# Antenna_Supervisory_Circuit.net
KiCad netlist of a schematic drawn in Altium Designer
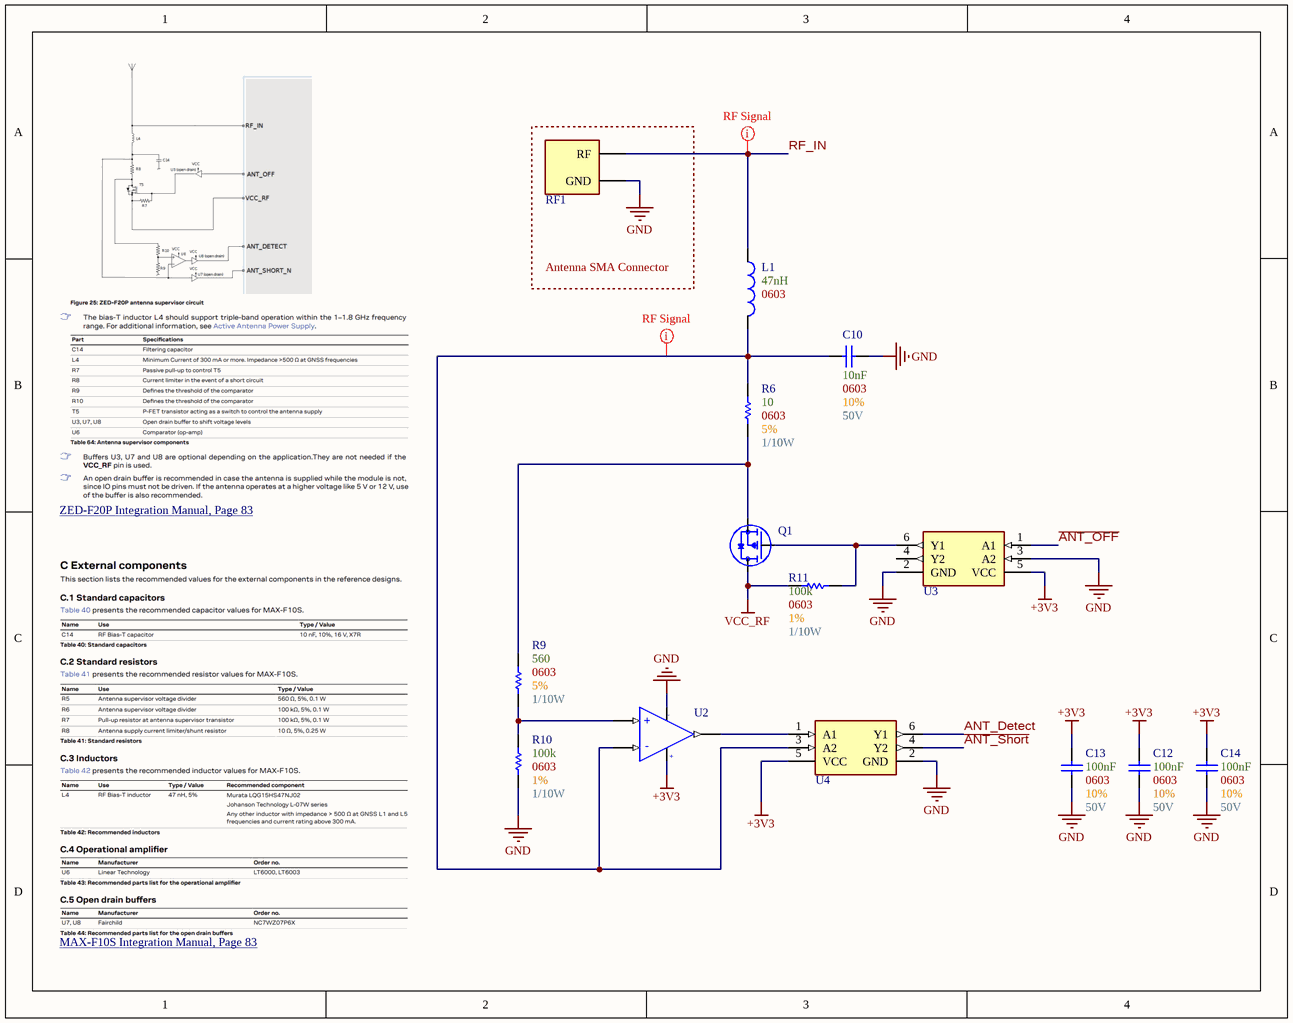
[diagram p0: Antenna Supervisory Circuit.SchDoc]

(export (version "E")
  (design (tool "Eeschema 10.0.6"))
  (components
    (comp (ref "C10")
      (value "[Cap] 0603 0.01uF 10% 50V")
      (footprint "[Cap] SMD 0603")
      (description "C0603C103K5RACTU")
      (fields
        (field (name "MAX VOLTAGE") "50V")
        (field (name "SIZE PACKAGE") "0603")
        (field (name "TOLERANCE") "10%")
        (field (name "CAPACITANCE") "10nF")
      )
      (libsource (lib "Capacitors") (part "[Cap] 0603 0.01uF 10% 50V"))
    )
    (comp (ref "C12")
      (value "[Cap] 0603 0.1uF 10% 50V")
      (footprint "[Cap] SMD 0603")
      (description "CL10B104KB8NNNC")
      (fields
        (field (name "MAX VOLTAGE") "50V")
        (field (name "SIZE PACKAGE") "0603")
        (field (name "TOLERANCE") "10%")
        (field (name "CAPACITANCE") "100nF")
      )
      (libsource (lib "Capacitors") (part "[Cap] 0603 0.1uF 10% 50V"))
    )
    (comp (ref "C13")
      (value "[Cap] 0603 0.1uF 10% 50V")
      (footprint "[Cap] SMD 0603")
      (description "CL10B104KB8NNNC")
      (fields
        (field (name "MAX VOLTAGE") "50V")
        (field (name "SIZE PACKAGE") "0603")
        (field (name "TOLERANCE") "10%")
        (field (name "CAPACITANCE") "100nF")
      )
      (libsource (lib "Capacitors") (part "[Cap] 0603 0.1uF 10% 50V"))
    )
    (comp (ref "C14")
      (value "[Cap] 0603 0.1uF 10% 50V")
      (footprint "[Cap] SMD 0603")
      (description "CL10B104KB8NNNC")
      (fields
        (field (name "MAX VOLTAGE") "50V")
        (field (name "SIZE PACKAGE") "0603")
        (field (name "TOLERANCE") "10%")
        (field (name "CAPACITANCE") "100nF")
      )
      (libsource (lib "Capacitors") (part "[Cap] 0603 0.1uF 10% 50V"))
    )
    (comp (ref "L1")
      (value "[47nH] SMD 0603 90mA")
      (footprint "[Inductor] SMD 0603")
      (description "AIMC-0603-47NJ-T")
      (fields (field (name "PACKAGE") "0603") (field (name "INDUCTANCE") "47nH"))
      (libsource (lib "Inductors") (part "[47nH] SMD 0603 90mA"))
    )
    (comp (ref "Q1")
      (value "[PMOS] SMD 20V 1A 200mOhm")
      (footprint "SOT323")
      (description "PMF170XP,115")
      (libsource (lib "Transistors") (part "[PMOS] SMD 20V 1A 200mOhm"))
    )
    (comp (ref "R6")
      (value "[10] SMD 0603 5% 1/10W")
      (footprint "[Res] SMD 0603")
      (description "RC0603JR-1310RL")
      (fields
        (field (name "WATTAGE") "1/10W")
        (field (name "TOLERANCE") "5%")
        (field (name "RESISTANCE") "10")
        (field (name "SIZE PACKAGE") "0603")
      )
      (libsource (lib "Resistors") (part "[10] SMD 0603 5% 1/10W"))
    )
    (comp (ref "R9")
      (value "[560] SMD 0603 5% 1/10W")
      (footprint "[Res] SMD 0603")
      (description "RC0603JR-07560RL")
      (fields
        (field (name "WATTAGE") "1/10W")
        (field (name "TOLERANCE") "5%")
        (field (name "RESISTANCE") "560")
        (field (name "SIZE PACKAGE") "0603")
      )
      (libsource (lib "Resistors") (part "[560] SMD 0603 5% 1/10W"))
    )
    (comp (ref "R10")
      (value "[100k] SMD 0603 1% 1/10W")
      (footprint "[Res] SMD 0603")
      (description "RC0603FR-07100KL")
      (fields
        (field (name "WATTAGE") "1/10W")
        (field (name "TOLERANCE") "1%")
        (field (name "RESISTANCE") "100k")
        (field (name "SIZE PACKAGE") "0603")
      )
      (libsource (lib "Resistors") (part "[100k] SMD 0603 1% 1/10W"))
    )
    (comp (ref "R11")
      (value "[100k] SMD 0603 1% 1/10W")
      (footprint "[Res] SMD 0603")
      (description "RC0603FR-07100KL")
      (fields
        (field (name "WATTAGE") "1/10W")
        (field (name "TOLERANCE") "1%")
        (field (name "RESISTANCE") "100k")
        (field (name "SIZE PACKAGE") "0603")
      )
      (libsource (lib "Resistors") (part "[100k] SMD 0603 1% 1/10W"))
    )
    (comp (ref "RF1")
      (value "[SMA] 90deg Thru-Hole")
      (footprint "[SMA] 90deg Thru-Hole")
      (description "RFPC-SMA27-F")
      (libsource (lib "Connectors") (part "[SMA] 90deg Thru-Hole"))
    )
    (comp (ref "U2")
      (value "[Op-Amp] Rail-to-Rail Vmax=16V GBP=3kHz")
      (footprint "[Op-Amp] Rail-to-Rail Vmax=16V GBP=3kHz")
      (description "LT6003CS5#TRMPBF")
      (libsource (lib "ICs") (part "[Op-Amp] Rail-to-Rail Vmax=16V GBP=3kHz"))
    )
    (comp (ref "U3")
      (value "[Buffer] Dual Open Drain")
      (footprint "[Buffer] Dual Open Drain")
      (description "NC7WZ07P6X")
      (libsource (lib "ICs") (part "[Buffer] Dual Open Drain"))
    )
    (comp (ref "U4")
      (value "[Buffer] Dual Open Drain")
      (footprint "[Buffer] Dual Open Drain")
      (description "NC7WZ07P6X")
      (libsource (lib "") (part "[Buffer] Dual Open Drain_1"))
    )
  )
  (nets
    (net (code "1") (name "+3V3") (class "Default")
      (node (ref "C12") (pin "2") (pinfunction "2_2") (pintype "passive"))
      (node (ref "C13") (pin "2") (pinfunction "2_2") (pintype "passive"))
      (node (ref "C14") (pin "2") (pinfunction "2_2") (pintype "passive"))
      (node (ref "U2") (pin "5") (pinfunction "V+_5") (pintype "power_in"))
      (node (ref "U3") (pin "5") (pinfunction "VCC_5") (pintype "power_in"))
      (node (ref "U4") (pin "5") (pinfunction "VCC_5") (pintype "power_in"))
    )
    (net (code "2") (name "/ANT_Detect") (class "Default")
      (node (ref "U4") (pin "6") (pinfunction "Y1_6") (pintype "output"))
    )
    (net (code "3") (name "/ANT_OFF") (class "Default")
      (node (ref "U3") (pin "1") (pinfunction "A1_1") (pintype "input"))
    )
    (net (code "4") (name "/ANT_Short") (class "Default")
      (node (ref "U4") (pin "4") (pinfunction "Y2_4") (pintype "output"))
    )
    (net (code "5") (name "/RF_IN") (class "Default")
      (node (ref "L1") (pin "1") (pinfunction "1_1") (pintype "passive"))
      (node (ref "RF1") (pin "1") (pinfunction "RF_1") (pintype "passive"))
    )
    (net (code "6") (name "GND") (class "Default")
      (node (ref "C10") (pin "1") (pinfunction "1_1") (pintype "passive"))
      (node (ref "C12") (pin "1") (pinfunction "1_1") (pintype "passive"))
      (node (ref "C13") (pin "1") (pinfunction "1_1") (pintype "passive"))
      (node (ref "C14") (pin "1") (pinfunction "1_1") (pintype "passive"))
      (node (ref "R10") (pin "1") (pinfunction "1_1") (pintype "passive"))
      (node (ref "RF1") (pin "2") (pinfunction "GND_2") (pintype "power_in"))
      (node (ref "U2") (pin "2") (pinfunction "V-_2") (pintype "power_in"))
      (node (ref "U3") (pin "2") (pinfunction "GND_2") (pintype "power_in"))
      (node (ref "U3") (pin "3") (pinfunction "A2_3") (pintype "input"))
      (node (ref "U4") (pin "2") (pinfunction "GND_2") (pintype "power_in"))
    )
    (net (code "7") (name "Net-(Q1-Drain)") (class "Default")
      (node (ref "Q1") (pin "3") (pinfunction "Drain_3") (pintype "passive"))
      (node (ref "R6") (pin "1") (pinfunction "1_1") (pintype "passive"))
      (node (ref "R9") (pin "2") (pinfunction "2_2") (pintype "passive"))
    )
    (net (code "8") (name "Net-(Q1-Gate)") (class "Default")
      (node (ref "Q1") (pin "1") (pinfunction "Gate_1") (pintype "passive"))
      (node (ref "R11") (pin "1") (pinfunction "1_1") (pintype "passive"))
      (node (ref "U3") (pin "6") (pinfunction "Y1_6") (pintype "output"))
    )
    (net (code "9") (name "Net-(U2-+IN)") (class "Default")
      (node (ref "R10") (pin "2") (pinfunction "2_2") (pintype "passive"))
      (node (ref "R9") (pin "1") (pinfunction "1_1") (pintype "passive"))
      (node (ref "U2") (pin "3") (pinfunction "+IN_3") (pintype "input"))
    )
    (net (code "10") (name "Net-(U2--IN)") (class "Default")
      (node (ref "C10") (pin "2") (pinfunction "2_2") (pintype "passive"))
      (node (ref "L1") (pin "2") (pinfunction "2_2") (pintype "passive"))
      (node (ref "R6") (pin "2") (pinfunction "2_2") (pintype "passive"))
      (node (ref "U2") (pin "4") (pinfunction "-IN_4") (pintype "input"))
      (node (ref "U4") (pin "3") (pinfunction "A2_3") (pintype "input"))
    )
    (net (code "11") (name "Net-(U2-OUT)") (class "Default")
      (node (ref "U2") (pin "1") (pinfunction "OUT_1") (pintype "output"))
      (node (ref "U4") (pin "1") (pinfunction "A1_1") (pintype "input"))
    )
    (net (code "12") (name "VCC_RF") (class "Default")
      (node (ref "Q1") (pin "2") (pinfunction "Source_2") (pintype "passive"))
      (node (ref "R11") (pin "2") (pinfunction "2_2") (pintype "passive"))
    )
    (net (code "13") (name "unconnected-(U3-Y2-Pad4)") (class "Default")
      (node (ref "U3") (pin "4") (pinfunction "Y2_4") (pintype "output"))
    )
  )
)
